# Power.net
KiCad netlist of a schematic drawn in Altium Designer
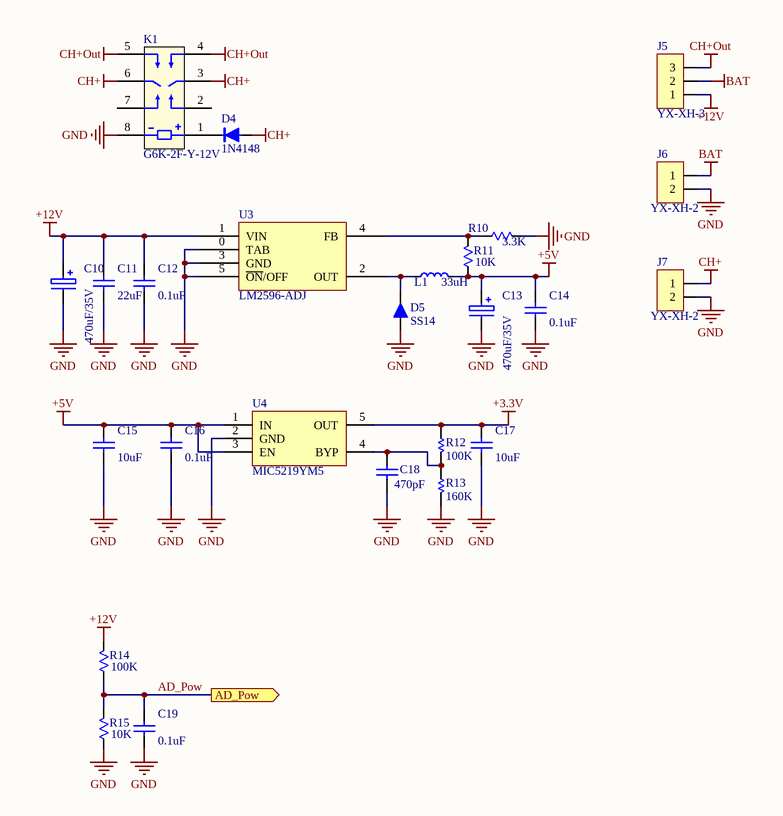
[diagram p0: 电子脚铐手持式主控板_Power.SchDoc]

(export (version "E")
  (design (tool "Eeschema 10.0.6"))
  (components
    (comp (ref "C10")
      (value "470uF/35V")
      (footprint "C10*10.8")
      (description "Electrolytic Capacitor")
      (libsource (lib "*") (part "ELECTRO"))
    )
    (comp (ref "C11")
      (value "22uF")
      (footprint "C1210")
      (description "CAP")
      (fields (field (name "PUBLISHER") "Altium Limited"))
      (libsource (lib "Passive Components Class") (part "CAP"))
    )
    (comp (ref "C12")
      (value "0.1uF")
      (footprint "C0603")
      (description "CAP")
      (fields (field (name "PUBLISHER") "Altium Limited"))
      (libsource (lib "Passive Components Class") (part "CAP"))
    )
    (comp (ref "C13")
      (value "470uF/35V")
      (footprint "C10*10.8")
      (description "Electrolytic Capacitor")
      (libsource (lib "*") (part "ELECTRO"))
    )
    (comp (ref "C14")
      (value "0.1uF")
      (footprint "C0603")
      (description "CAP")
      (fields (field (name "PUBLISHER") "Altium Limited"))
      (libsource (lib "Passive Components Class") (part "CAP"))
    )
    (comp (ref "C15")
      (value "10uF")
      (footprint "C0603")
      (description "CAP")
      (fields (field (name "PUBLISHER") "Altium Limited"))
      (libsource (lib "Passive Components Class") (part "CAP"))
    )
    (comp (ref "C16")
      (value "0.1uF")
      (footprint "C0603")
      (description "CAP")
      (fields (field (name "PUBLISHER") "Altium Limited"))
      (libsource (lib "Passive Components Class") (part "CAP"))
    )
    (comp (ref "C17")
      (value "10uF")
      (footprint "C0603")
      (description "CAP")
      (fields (field (name "PUBLISHER") "Altium Limited"))
      (libsource (lib "Passive Components Class") (part "CAP"))
    )
    (comp (ref "C18")
      (value "470pF")
      (footprint "C0603")
      (description "CAP")
      (fields (field (name "PUBLISHER") "Altium Limited"))
      (libsource (lib "Passive Components Class") (part "CAP"))
    )
    (comp (ref "C19")
      (value "0.1uF")
      (footprint "C0603")
      (description "CAP")
      (fields (field (name "PUBLISHER") "Altium Limited"))
      (libsource (lib "Passive Components Class") (part "CAP"))
    )
    (comp (ref "D4")
      (value "1N4148")
      (footprint "SOD-80-S")
      (description "Silicon Epitaxial Planar Diodes")
      (libsource (lib "Passive Components Class") (part "DIODE-SWITCHING"))
    )
    (comp (ref "D5")
      (value "SS14")
      (footprint "SMA")
      (description "High Conductance Fast Diode")
      (fields (field (name "PUBLISHER") "Altium Limited"))
      (libsource (lib "爬壁机器人本体主控") (part "Diode 1N4148"))
    )
    (comp (ref "J5")
      (value "YX-XH-3")
      (footprint "YX-XH-3")
      (libsource (lib "Connector Class") (part "HEADER1X3"))
    )
    (comp (ref "J6")
      (value "YX-XH-2")
      (footprint "YX-XH-2")
      (description "插座")
      (libsource (lib "Connector") (part "Jack 1x2"))
    )
    (comp (ref "J7")
      (value "YX-XH-2")
      (footprint "YX-XH-2")
      (description "插座")
      (libsource (lib "Connector") (part "Jack 1x2"))
    )
    (comp (ref "K1")
      (value "G6K-2F-Y-12V")
      (footprint "G6K-2F-Y")
      (libsource (lib "Productor Class") (part "G6K-2F-Y"))
    )
    (comp (ref "L1")
      (value "33uH")
      (footprint "L10.5*11.5mm")
      (description "INDUCTOR")
      (fields (field (name "PUBLISHER") "Altium Limited"))
      (libsource (lib "Passive Components Class") (part "INDUCTOR"))
    )
    (comp (ref "R10")
      (value "3.3K")
      (footprint "R0603")
      (description "Resistor")
      (fields (field (name "PUBLISHER") "Altium Limited"))
      (libsource (lib "Passive Components Class") (part "RES"))
    )
    (comp (ref "R11")
      (value "10K")
      (footprint "R0603")
      (description "Resistor")
      (fields (field (name "PUBLISHER") "Altium Limited"))
      (libsource (lib "Passive Components Class") (part "RES"))
    )
    (comp (ref "R12") (value "100K") (footprint "R0603") (libsource (lib "RLCYDF") (part "Res")))
    (comp (ref "R13") (value "160K") (footprint "R0603") (libsource (lib "RLCYDF") (part "Res")))
    (comp (ref "R14")
      (value "100K")
      (footprint "R0603")
      (description "Resistor")
      (fields (field (name "PUBLISHER") "Altium Limited"))
      (libsource (lib "Passive Components Class") (part "RES"))
    )
    (comp (ref "R15")
      (value "10K")
      (footprint "R0603")
      (description "Resistor")
      (fields (field (name "PUBLISHER") "Altium Limited"))
      (libsource (lib "Passive Components Class") (part "RES"))
    )
    (comp (ref "U3")
      (value "LM2596-ADJ")
      (footprint "TO-263-5")
      (description "LM2596-5;LM2576-5")
      (libsource (lib "chip") (part "LM25x6-5"))
    )
    (comp (ref "U4") (value "MIC5219YM5") (footprint "SOT-23-5") (libsource (lib "Power") (part "MIC5205")))
  )
  (nets
    (net (code "1") (name "+3.3V") (class "Default")
      (node (ref "C17") (pin "1") (pinfunction "1_1") (pintype "passive"))
      (node (ref "R12") (pin "1") (pinfunction "1_1") (pintype "passive"))
      (node (ref "U4") (pin "5") (pinfunction "OUT_5") (pintype "passive"))
    )
    (net (code "2") (name "+5V") (class "Default")
      (node (ref "C13") (pin "1") (pinfunction "1_1") (pintype "passive"))
      (node (ref "C14") (pin "1") (pinfunction "1_1") (pintype "passive"))
      (node (ref "C15") (pin "1") (pinfunction "1_1") (pintype "passive"))
      (node (ref "C16") (pin "1") (pinfunction "1_1") (pintype "passive"))
      (node (ref "L1") (pin "2") (pinfunction "2_2") (pintype "passive"))
      (node (ref "R11") (pin "1") (pinfunction "1_1") (pintype "passive"))
      (node (ref "U4") (pin "1") (pinfunction "IN_1") (pintype "passive"))
      (node (ref "U4") (pin "3") (pinfunction "EN_3") (pintype "passive"))
    )
    (net (code "3") (name "+12V") (class "Default")
      (node (ref "C10") (pin "1") (pinfunction "1_1") (pintype "passive"))
      (node (ref "C11") (pin "1") (pinfunction "1_1") (pintype "passive"))
      (node (ref "C12") (pin "1") (pinfunction "1_1") (pintype "passive"))
      (node (ref "J5") (pin "1") (pinfunction "1_1") (pintype "passive"))
      (node (ref "R14") (pin "2") (pinfunction "2_2") (pintype "passive"))
      (node (ref "U3") (pin "1") (pinfunction "VIN_1") (pintype "passive"))
    )
    (net (code "4") (name "/AD_Pow") (class "Default")
      (node (ref "C19") (pin "1") (pinfunction "1_1") (pintype "passive"))
      (node (ref "R14") (pin "1") (pinfunction "1_1") (pintype "passive"))
      (node (ref "R15") (pin "2") (pinfunction "2_2") (pintype "passive"))
    )
    (net (code "5") (name "BAT") (class "Default")
      (node (ref "J5") (pin "2") (pinfunction "2_2") (pintype "passive"))
      (node (ref "J6") (pin "1") (pinfunction "1_1") (pintype "passive"))
    )
    (net (code "6") (name "CH+") (class "Default")
      (node (ref "D4") (pin "1") (pinfunction "A_1") (pintype "passive"))
      (node (ref "J7") (pin "1") (pinfunction "1_1") (pintype "passive"))
      (node (ref "K1") (pin "3") (pinfunction "3_3") (pintype "passive"))
      (node (ref "K1") (pin "6") (pinfunction "6_6") (pintype "passive"))
    )
    (net (code "7") (name "CH+Out") (class "Default")
      (node (ref "J5") (pin "3") (pinfunction "3_3") (pintype "passive"))
      (node (ref "K1") (pin "4") (pinfunction "4_4") (pintype "passive"))
      (node (ref "K1") (pin "5") (pinfunction "5_5") (pintype "passive"))
    )
    (net (code "8") (name "GND") (class "Default")
      (node (ref "C10") (pin "2") (pinfunction "2_2") (pintype "passive"))
      (node (ref "C11") (pin "2") (pinfunction "2_2") (pintype "passive"))
      (node (ref "C12") (pin "2") (pinfunction "2_2") (pintype "passive"))
      (node (ref "C13") (pin "2") (pinfunction "2_2") (pintype "passive"))
      (node (ref "C14") (pin "2") (pinfunction "2_2") (pintype "passive"))
      (node (ref "C15") (pin "2") (pinfunction "2_2") (pintype "passive"))
      (node (ref "C16") (pin "2") (pinfunction "2_2") (pintype "passive"))
      (node (ref "C17") (pin "2") (pinfunction "2_2") (pintype "passive"))
      (node (ref "C18") (pin "2") (pinfunction "2_2") (pintype "passive"))
      (node (ref "C19") (pin "2") (pinfunction "2_2") (pintype "passive"))
      (node (ref "D5") (pin "1") (pinfunction "A_1") (pintype "passive"))
      (node (ref "J6") (pin "2") (pinfunction "2_2") (pintype "passive"))
      (node (ref "J7") (pin "2") (pinfunction "2_2") (pintype "passive"))
      (node (ref "K1") (pin "8") (pinfunction "8_8") (pintype "passive"))
      (node (ref "R10") (pin "2") (pinfunction "2_2") (pintype "passive"))
      (node (ref "R13") (pin "2") (pinfunction "2_2") (pintype "passive"))
      (node (ref "R15") (pin "1") (pinfunction "1_1") (pintype "passive"))
      (node (ref "U3") (pin "0") (pinfunction "TAB_0") (pintype "passive"))
      (node (ref "U3") (pin "3") (pinfunction "GND_3") (pintype "passive"))
      (node (ref "U3") (pin "5") (pinfunction "~{ON}/OFF_5") (pintype "passive"))
      (node (ref "U4") (pin "2") (pinfunction "GND_2") (pintype "passive"))
    )
    (net (code "9") (name "Net-(D4-K)") (class "Default")
      (node (ref "D4") (pin "2") (pinfunction "K_2") (pintype "passive"))
      (node (ref "K1") (pin "1") (pinfunction "1_1") (pintype "passive"))
    )
    (net (code "10") (name "Net-(D5-K)") (class "Default")
      (node (ref "D5") (pin "2") (pinfunction "K_2") (pintype "passive"))
      (node (ref "L1") (pin "1") (pinfunction "1_1") (pintype "passive"))
      (node (ref "U3") (pin "2") (pinfunction "OUT_2") (pintype "passive"))
    )
    (net (code "11") (name "Net-(U3-FB)") (class "Default")
      (node (ref "R10") (pin "1") (pinfunction "1_1") (pintype "passive"))
      (node (ref "R11") (pin "2") (pinfunction "2_2") (pintype "passive"))
      (node (ref "U3") (pin "4") (pinfunction "FB_4") (pintype "passive"))
    )
    (net (code "12") (name "Net-(U4-BYP)") (class "Default")
      (node (ref "C18") (pin "1") (pinfunction "1_1") (pintype "passive"))
      (node (ref "R12") (pin "2") (pinfunction "2_2") (pintype "passive"))
      (node (ref "R13") (pin "1") (pinfunction "1_1") (pintype "passive"))
      (node (ref "U4") (pin "4") (pinfunction "BYP_4") (pintype "passive"))
    )
    (net (code "13") (name "unconnected-(K1-Pad2)") (class "Default")
      (node (ref "K1") (pin "2") (pinfunction "2_2") (pintype "passive"))
    )
    (net (code "14") (name "unconnected-(K1-Pad7)") (class "Default")
      (node (ref "K1") (pin "7") (pinfunction "7_7") (pintype "passive"))
    )
  )
)
